# TEST-MODULE-V3.net
KiCad netlist of a schematic drawn in Altium Designer
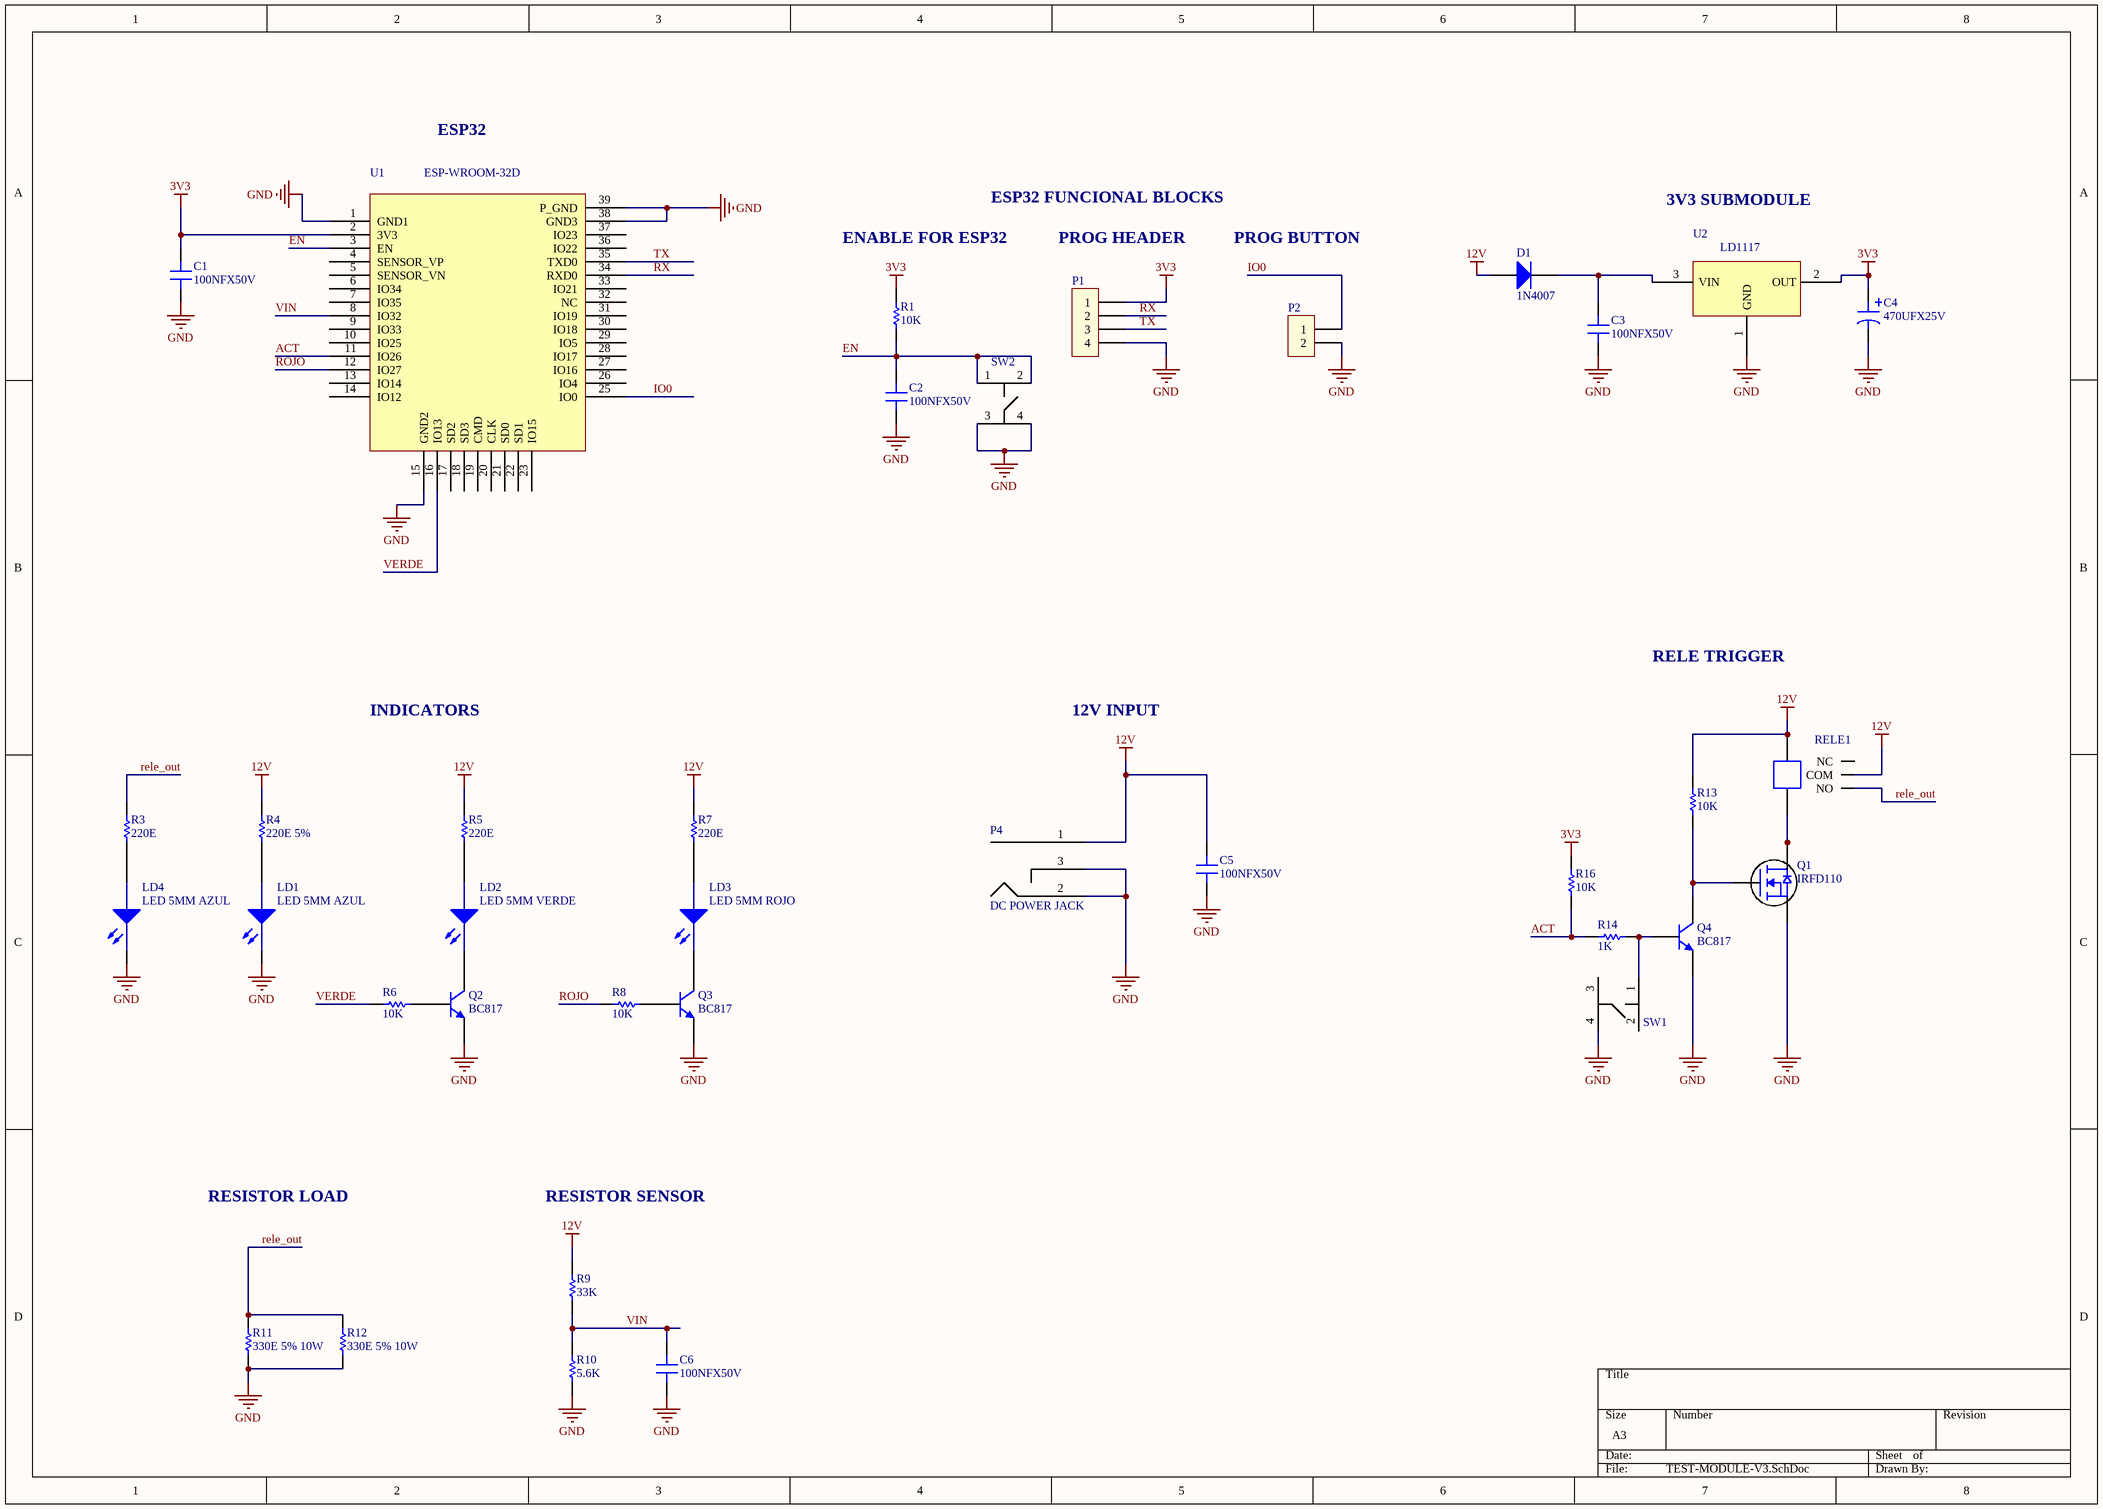
[diagram p0: TEST-MODULE-V3.SchDoc]

(export (version "E")
  (design (tool "Eeschema 10.0.6"))
  (components
    (comp (ref "C1")
      (value "100NFX50V")
      (footprint "CAP.SMD.0805")
      (description "100NFX50V X7R 10% CER.MULT. SMD 0805")
      (libsource (lib "Libreria-Capacitores") (part "Capacitor 100NFX50V X7R 10% CER.MULT. SMD 0805"))
    )
    (comp (ref "C2")
      (value "100NFX50V")
      (footprint "CAP.SMD.0805")
      (description "100NFX50V X7R 10% CER.MULT. SMD 0805")
      (libsource (lib "Libreria-Capacitores") (part "Capacitor 100NFX50V X7R 10% CER.MULT. SMD 0805"))
    )
    (comp (ref "C3")
      (value "100NFX50V")
      (footprint "CAP.SMD.0805")
      (description "100NFX50V X7R 10% CER.MULT. SMD 0805")
      (libsource (lib "Libreria-Capacitores") (part "Capacitor 100NFX50V X7R 10% CER.MULT. SMD 0805"))
    )
    (comp (ref "C4")
      (value "470UFX25V")
      (footprint "CAP-ELEC-10X13")
      (description "470UFX25V 85°C 10x13 ELE.RAD")
      (libsource (lib "Libreria-Capacitores") (part "Capacitor Electrolitico 470UFX25V 85°C 10x13 ELE.RAD"))
    )
    (comp (ref "C5")
      (value "100NFX50V")
      (footprint "CAP.SMD.0805")
      (description "100NFX50V X7R 10% CER.MULT. SMD 0805")
      (libsource (lib "Libreria-Capacitores") (part "Capacitor 100NFX50V X7R 10% CER.MULT. SMD 0805"))
    )
    (comp (ref "C6")
      (value "100NFX50V")
      (footprint "CAP.SMD.0805")
      (description "100NFX50V X7R 10% CER.MULT. SMD 0805")
      (libsource (lib "Libreria-Capacitores") (part "Capacitor 100NFX50V X7R 10% CER.MULT. SMD 0805"))
    )
    (comp (ref "D1")
      (value "1N4007")
      (footprint "Diode DO41")
      (description "Diodo 1N4007 DIODO 1A 1000V DO41")
      (libsource (lib "Libreria-Diodos") (part "Diodo 1N4007 DIODO 1A 1000V DO41"))
    )
    (comp (ref "LD1")
      (value "LED 5MM AZUL")
      (footprint "LED-5MM-ALTO-9-AZUL")
      (description "LED 5MM AZUL ALTO 9")
      (libsource (lib "Libreria-LEDs") (part "LED 5MM AZUL ALTO 9"))
    )
    (comp (ref "LD2")
      (value "LED 5MM VERDE")
      (footprint "LED-5MM-ALTO-9-VERDE")
      (description "LED 5MM VERDE ALTO 9")
      (libsource (lib "Libreria-LEDs") (part "LED 5MM VERDE ALTO 9"))
    )
    (comp (ref "LD3")
      (value "LED 5MM ROJO")
      (footprint "LED-5MM-ALTO-9-ROJO")
      (description "LED 5MM ROJO ALTO 9")
      (libsource (lib "Libreria-LEDs") (part "LED 5MM ROJO ALTO 9"))
    )
    (comp (ref "LD4")
      (value "LED 5MM AZUL")
      (footprint "LED-5MM-ALTO-9-AZUL")
      (description "LED 5MM AZUL ALTO 9")
      (libsource (lib "Libreria-LEDs") (part "LED 5MM AZUL ALTO 9"))
    )
    (comp (ref "P1")
      (value "IDC-HE-THT-1X4-P2.54MM")
      (footprint "IDC-HE-THT-1X4-P2.54MM")
      (libsource (lib "Libreria-Conectores") (part "IDC-HE-THT-1X4-P2.54MM"))
    )
    (comp (ref "P2")
      (value "IDC-MA-THT-1X2-P2.54MM-L11")
      (footprint "IDC-MA-THT-1X2-P2.54MM-L11")
      (libsource (lib "Libreria-Conectores") (part "IDC-MA-THT-1X2-P2.54MM-L11"))
    )
    (comp (ref "P4")
      (value "DC POWER JACK")
      (footprint "VAR-DC-JACK - VERT")
      (description "DC POWER JACK VERTICAL 2MM")
      (libsource (lib "Libreria-Varios") (part "DC POWER JACK VERTICAL 2MM"))
    )
    (comp (ref "Q1")
      (value "IRFD110")
      (footprint "TRA-IRFD110")
      (description "Transistor MOSFET N IRFD110")
      (libsource (lib "Libreria-Transistores") (part "Transistor MOSFET N IRFD110"))
    )
    (comp (ref "Q2")
      (value "BC817")
      (footprint "NPN.SMD.SOT23")
      (description "BC817-40 TRA.NPN 45V0.5A 0.25W SOT23")
      (libsource (lib "Libreria-Transistores") (part "Transistor BC817-40 TRA.NPN 45V0.5A 0.25W SOT23"))
    )
    (comp (ref "Q3")
      (value "BC817")
      (footprint "NPN.SMD.SOT23")
      (description "BC817-40 TRA.NPN 45V0.5A 0.25W SOT23")
      (libsource (lib "Libreria-Transistores") (part "Transistor BC817-40 TRA.NPN 45V0.5A 0.25W SOT23"))
    )
    (comp (ref "Q4")
      (value "BC817")
      (footprint "NPN.SMD.SOT23")
      (description "BC817-40 TRA.NPN 45V0.5A 0.25W SOT23")
      (libsource (lib "Libreria-Transistores") (part "Transistor BC817-40 TRA.NPN 45V0.5A 0.25W SOT23"))
    )
    (comp (ref "R1")
      (value "10K")
      (footprint "RES.SMD.103")
      (description "10K 5% 0805 1/8W RES.SMD")
      (libsource (lib "Libreria-Resistencias") (part "Resistencia 10K 5% 0805 1/8W"))
    )
    (comp (ref "R3")
      (value "220E")
      (footprint "RES.SMD.221")
      (description "220E 5% 0805 1/8W RES.SMD")
      (libsource (lib "Libreria-Resistencias") (part "Resistencia 220E 5% 0805 1/8W"))
    )
    (comp (ref "R4")
      (value "220E 5%")
      (footprint "RES.SMD.221")
      (description "220E 5% 0805 1/8W RES.SMD")
      (libsource (lib "Libreria-Resistencias") (part "Resistencia 220E 5% 0805 1/8W"))
    )
    (comp (ref "R5")
      (value "220E")
      (footprint "RES.SMD.221")
      (description "220E 5% 0805 1/8W RES.SMD")
      (libsource (lib "Libreria-Resistencias") (part "Resistencia 220E 5% 0805 1/8W"))
    )
    (comp (ref "R6")
      (value "10K")
      (footprint "RES.SMD.103")
      (description "10K 5% 0805 1/8W RES.SMD")
      (libsource (lib "Libreria-Resistencias") (part "Resistencia 10K 5% 0805 1/8W"))
    )
    (comp (ref "R7")
      (value "220E")
      (footprint "RES.SMD.221")
      (description "220E 5% 0805 1/8W RES.SMD")
      (libsource (lib "Libreria-Resistencias") (part "Resistencia 220E 5% 0805 1/8W"))
    )
    (comp (ref "R8")
      (value "10K")
      (footprint "RES.SMD.103")
      (description "10K 5% 0805 1/8W RES.SMD")
      (libsource (lib "Libreria-Resistencias") (part "Resistencia 10K 5% 0805 1/8W"))
    )
    (comp (ref "R9")
      (value "33K")
      (footprint "RES.SMD.333")
      (description "33K 5% 0805 1/8W RES.SMD")
      (libsource (lib "Libreria-Resistencias") (part "Resistencia 33K 5% 0805 1/8W"))
    )
    (comp (ref "R10")
      (value "5.6K")
      (footprint "RES.SMD.562")
      (description "5.6K 5% 0805 1/8W RES.SMD")
      (libsource (lib "Libreria-Resistencias") (part "Resistencia 5.6K 5% 0805 1/8W"))
    )
    (comp (ref "R11")
      (value "330E 5% 10W")
      (footprint "RES-CERAMICA-10W")
      (description "Resistencia Ceramica 330E 5% 10W SE15 RES.CEM")
      (libsource (lib "Libreria-Resistencias") (part "Resistencia Ceramica 330E 5% 10W SE15 RES.CEM"))
    )
    (comp (ref "R12")
      (value "330E 5% 10W")
      (footprint "RES-CERAMICA-10W")
      (description "Resistencia Ceramica 330E 5% 10W SE15 RES.CEM")
      (libsource (lib "Libreria-Resistencias") (part "Resistencia Ceramica 330E 5% 10W SE15 RES.CEM"))
    )
    (comp (ref "R13")
      (value "10K")
      (footprint "RES.SMD.103")
      (description "10K 5% 0805 1/8W RES.SMD")
      (libsource (lib "Libreria-Resistencias") (part "Resistencia 10K 5% 0805 1/8W"))
    )
    (comp (ref "R14")
      (value "1K")
      (footprint "RES.SMD.102")
      (description "1K 5% 0805 1/8W RES.SMD")
      (libsource (lib "Libreria-Resistencias") (part "Resistencia 1K 5% 0805 1/8W"))
    )
    (comp (ref "R16")
      (value "10K")
      (footprint "RES.SMD.103")
      (description "10K 5% 0805 1/8W RES.SMD")
      (libsource (lib "Libreria-Resistencias") (part "Resistencia 10K 5% 0805 1/8W"))
    )
    (comp (ref "RELE1")
      (value "Relay simple inversor 12V 12A")
      (footprint "RELAY 12V 12A CHICO")
      (libsource (lib "Libreria-Varios") (part "VAR-RELE-12V Relay simple inversor chico 12V 12A"))
    )
    (comp (ref "SW1")
      (value "TACT-SWITCH-THT-4C-06X06(13MM)-JIANFU")
      (footprint "TACT-SWITCH-THT-4C-06X06-13MM")
      (libsource (lib "Libreria-Switches") (part "TACT-SWITCH-THT-4C-06X06(13MM)-JIANFU"))
    )
    (comp (ref "SW2")
      (value "TACT-SWITCH-THT-4C-06X06(5MM)")
      (footprint "TACT-SWITCH-THT-4C-06X06-5MM")
      (libsource (lib "Libreria-Switches") (part "TACT-SWITCH-THT-4C-06X06(5MM)"))
    )
    (comp (ref "U1")
      (value "ESP32-WROOM-32D")
      (footprint "ESP32-WROOM-32D")
      (libsource (lib "Libreria-Semiconductores") (part "ESP32-WROOM-32D"))
    )
    (comp (ref "U2")
      (value "LD1117S33TR SMD DPAK 0.8A 3.3V LDO LINEAR REGULATOR")
      (footprint "DPAK")
      (libsource (lib "Libreria-Semiconductores") (part "LD1117S33TR SMD DPAK 0.8A 3.3V LDO LINEAR REGULATOR"))
    )
  )
  (nets
    (net (code "1") (name "/ACT") (class "Default")
      (node (ref "R14") (pin "1") (pinfunction "1_1") (pintype "passive"))
      (node (ref "R16") (pin "1") (pinfunction "1_1") (pintype "passive"))
      (node (ref "U1") (pin "11") (pinfunction "IO26_11") (pintype "passive"))
    )
    (net (code "2") (name "/EN") (class "Default")
      (node (ref "C2") (pin "2") (pinfunction "2_2") (pintype "passive"))
      (node (ref "R1") (pin "1") (pinfunction "1_1") (pintype "passive"))
      (node (ref "SW2") (pin "1") (pinfunction "1_1") (pintype "passive"))
      (node (ref "SW2") (pin "2") (pinfunction "2_2") (pintype "passive"))
      (node (ref "U1") (pin "3") (pinfunction "EN_3") (pintype "passive"))
    )
    (net (code "3") (name "/IO0") (class "Default")
      (node (ref "P2") (pin "1") (pinfunction "1_1") (pintype "passive"))
      (node (ref "U1") (pin "25") (pinfunction "IO0_25") (pintype "passive"))
    )
    (net (code "4") (name "/ROJO") (class "Default")
      (node (ref "R8") (pin "2") (pinfunction "2_2") (pintype "passive"))
      (node (ref "U1") (pin "12") (pinfunction "IO27_12") (pintype "passive"))
    )
    (net (code "5") (name "/RX") (class "Default")
      (node (ref "P1") (pin "2") (pinfunction "2_2") (pintype "passive"))
      (node (ref "U1") (pin "34") (pinfunction "RXD0_34") (pintype "passive"))
    )
    (net (code "6") (name "/TX") (class "Default")
      (node (ref "P1") (pin "3") (pinfunction "3_3") (pintype "passive"))
      (node (ref "U1") (pin "35") (pinfunction "TXD0_35") (pintype "passive"))
    )
    (net (code "7") (name "/VERDE") (class "Default")
      (node (ref "R6") (pin "1") (pinfunction "1_1") (pintype "passive"))
      (node (ref "U1") (pin "16") (pinfunction "IO13_16") (pintype "passive"))
    )
    (net (code "8") (name "/VIN") (class "Default")
      (node (ref "C6") (pin "2") (pinfunction "2_2") (pintype "passive"))
      (node (ref "R10") (pin "2") (pinfunction "2_2") (pintype "passive"))
      (node (ref "R9") (pin "1") (pinfunction "1_1") (pintype "passive"))
      (node (ref "U1") (pin "8") (pinfunction "IO32_8") (pintype "passive"))
    )
    (net (code "9") (name "/rele_out") (class "Default")
      (node (ref "R11") (pin "2") (pinfunction "2_2") (pintype "passive"))
      (node (ref "R12") (pin "2") (pinfunction "2_2") (pintype "passive"))
      (node (ref "R3") (pin "2") (pinfunction "2_2") (pintype "passive"))
      (node (ref "RELE1") (pin "4") (pinfunction "NO_4") (pintype "passive"))
    )
    (net (code "10") (name "3V3") (class "Default")
      (node (ref "C1") (pin "2") (pinfunction "2_2") (pintype "passive"))
      (node (ref "C4") (pin "1") (pinfunction "1_1") (pintype "passive"))
      (node (ref "P1") (pin "1") (pinfunction "1_1") (pintype "passive"))
      (node (ref "R1") (pin "2") (pinfunction "2_2") (pintype "passive"))
      (node (ref "R16") (pin "2") (pinfunction "2_2") (pintype "passive"))
      (node (ref "U1") (pin "2") (pinfunction "3V3_2") (pintype "passive"))
      (node (ref "U2") (pin "2") (pinfunction "OUT_2") (pintype "passive"))
    )
    (net (code "11") (name "12V") (class "Default")
      (node (ref "C5") (pin "2") (pinfunction "2_2") (pintype "passive"))
      (node (ref "D1") (pin "A") (pinfunction "A_A") (pintype "passive"))
      (node (ref "P4") (pin "1") (pinfunction "1_1") (pintype "passive"))
      (node (ref "R13") (pin "2") (pinfunction "2_2") (pintype "passive"))
      (node (ref "R4") (pin "2") (pinfunction "2_2") (pintype "passive"))
      (node (ref "R5") (pin "2") (pinfunction "2_2") (pintype "passive"))
      (node (ref "R7") (pin "2") (pinfunction "2_2") (pintype "passive"))
      (node (ref "R9") (pin "2") (pinfunction "2_2") (pintype "passive"))
      (node (ref "RELE1") (pin "1") (pinfunction "1_1") (pintype "passive"))
      (node (ref "RELE1") (pin "3") (pinfunction "COM_3") (pintype "passive"))
    )
    (net (code "12") (name "GND") (class "Default")
      (node (ref "C1") (pin "1") (pinfunction "1_1") (pintype "passive"))
      (node (ref "C2") (pin "1") (pinfunction "1_1") (pintype "passive"))
      (node (ref "C3") (pin "1") (pinfunction "1_1") (pintype "passive"))
      (node (ref "C4") (pin "2") (pinfunction "2_2") (pintype "passive"))
      (node (ref "C5") (pin "1") (pinfunction "1_1") (pintype "passive"))
      (node (ref "C6") (pin "1") (pinfunction "1_1") (pintype "passive"))
      (node (ref "LD1") (pin "K") (pinfunction "KB_K") (pintype "passive"))
      (node (ref "LD4") (pin "K") (pinfunction "KB_K") (pintype "passive"))
      (node (ref "P1") (pin "4") (pinfunction "4_4") (pintype "passive"))
      (node (ref "P2") (pin "2") (pinfunction "2_2") (pintype "passive"))
      (node (ref "P4") (pin "2") (pinfunction "2_2") (pintype "passive"))
      (node (ref "P4") (pin "3") (pinfunction "3_3") (pintype "passive"))
      (node (ref "Q1") (pin "4") (pinfunction "4_4") (pintype "passive"))
      (node (ref "Q2") (pin "2") (pinfunction "E_2") (pintype "passive"))
      (node (ref "Q3") (pin "2") (pinfunction "E_2") (pintype "passive"))
      (node (ref "Q4") (pin "2") (pinfunction "E_2") (pintype "passive"))
      (node (ref "R10") (pin "1") (pinfunction "1_1") (pintype "passive"))
      (node (ref "R11") (pin "1") (pinfunction "1_1") (pintype "passive"))
      (node (ref "R12") (pin "1") (pinfunction "1_1") (pintype "passive"))
      (node (ref "SW1") (pin "4") (pinfunction "4_4") (pintype "passive"))
      (node (ref "SW2") (pin "3") (pinfunction "3_3") (pintype "passive"))
      (node (ref "SW2") (pin "4") (pinfunction "4_4") (pintype "passive"))
      (node (ref "U1") (pin "1") (pinfunction "GND1_1") (pintype "passive"))
      (node (ref "U1") (pin "15") (pinfunction "GND2_15") (pintype "passive"))
      (node (ref "U1") (pin "38") (pinfunction "GND3_38") (pintype "passive"))
      (node (ref "U1") (pin "39") (pinfunction "P_GND_39") (pintype "passive"))
      (node (ref "U2") (pin "1") (pinfunction "GND_1") (pintype "passive"))
    )
    (net (code "13") (name "Net-(LD1-AB)") (class "Default")
      (node (ref "LD1") (pin "A") (pinfunction "AB_A") (pintype "passive"))
      (node (ref "R4") (pin "1") (pinfunction "1_1") (pintype "passive"))
    )
    (net (code "14") (name "Net-(LD2-AB)") (class "Default")
      (node (ref "LD2") (pin "A") (pinfunction "AB_A") (pintype "passive"))
      (node (ref "R5") (pin "1") (pinfunction "1_1") (pintype "passive"))
    )
    (net (code "15") (name "Net-(LD2-KB)") (class "Default")
      (node (ref "LD2") (pin "K") (pinfunction "KB_K") (pintype "passive"))
      (node (ref "Q2") (pin "3") (pinfunction "C_3") (pintype "passive"))
    )
    (net (code "16") (name "Net-(LD3-AB)") (class "Default")
      (node (ref "LD3") (pin "A") (pinfunction "AB_A") (pintype "passive"))
      (node (ref "R7") (pin "1") (pinfunction "1_1") (pintype "passive"))
    )
    (net (code "17") (name "Net-(LD3-KB)") (class "Default")
      (node (ref "LD3") (pin "K") (pinfunction "KB_K") (pintype "passive"))
      (node (ref "Q3") (pin "3") (pinfunction "C_3") (pintype "passive"))
    )
    (net (code "18") (name "Net-(LD4-AB)") (class "Default")
      (node (ref "LD4") (pin "A") (pinfunction "AB_A") (pintype "passive"))
      (node (ref "R3") (pin "1") (pinfunction "1_1") (pintype "passive"))
    )
    (net (code "19") (name "Net-(Q1-Pad1)") (class "Default")
      (node (ref "Q1") (pin "1") (pinfunction "1_1") (pintype "passive"))
      (node (ref "Q1") (pin "2") (pinfunction "2_2") (pintype "passive"))
      (node (ref "RELE1") (pin "2") (pinfunction "2_2") (pintype "passive"))
    )
    (net (code "20") (name "Net-(Q2-B)") (class "Default")
      (node (ref "Q2") (pin "1") (pinfunction "B_1") (pintype "passive"))
      (node (ref "R6") (pin "2") (pinfunction "2_2") (pintype "passive"))
    )
    (net (code "21") (name "Net-(Q3-B)") (class "Default")
      (node (ref "Q3") (pin "1") (pinfunction "B_1") (pintype "passive"))
      (node (ref "R8") (pin "1") (pinfunction "1_1") (pintype "passive"))
    )
    (net (code "22") (name "Net-(Q4-B)") (class "Default")
      (node (ref "Q4") (pin "1") (pinfunction "B_1") (pintype "passive"))
      (node (ref "R14") (pin "2") (pinfunction "2_2") (pintype "passive"))
      (node (ref "SW1") (pin "1") (pinfunction "1_1") (pintype "passive"))
    )
    (net (code "23") (name "Net-(Q4-C)") (class "Default")
      (node (ref "Q1") (pin "3") (pinfunction "3_3") (pintype "passive"))
      (node (ref "Q4") (pin "3") (pinfunction "C_3") (pintype "passive"))
      (node (ref "R13") (pin "1") (pinfunction "1_1") (pintype "passive"))
    )
    (net (code "24") (name "Net-(U2-VIN)") (class "Default")
      (node (ref "C3") (pin "2") (pinfunction "2_2") (pintype "passive"))
      (node (ref "D1") (pin "K") (pinfunction "K_K") (pintype "passive"))
      (node (ref "U2") (pin "3") (pinfunction "VIN_3") (pintype "passive"))
    )
    (net (code "25") (name "unconnected-(RELE1-NC-Pad5)") (class "Default")
      (node (ref "RELE1") (pin "5") (pinfunction "NC_5") (pintype "passive"))
    )
    (net (code "26") (name "unconnected-(SW1-Pad2)") (class "Default")
      (node (ref "SW1") (pin "2") (pinfunction "2_2") (pintype "passive"))
    )
    (net (code "27") (name "unconnected-(SW1-Pad3)") (class "Default")
      (node (ref "SW1") (pin "3") (pinfunction "3_3") (pintype "passive"))
    )
    (net (code "28") (name "unconnected-(U1-CLK-Pad20)") (class "Default")
      (node (ref "U1") (pin "20") (pinfunction "CLK_20") (pintype "passive"))
    )
    (net (code "29") (name "unconnected-(U1-CMD-Pad19)") (class "Default")
      (node (ref "U1") (pin "19") (pinfunction "CMD_19") (pintype "passive"))
    )
    (net (code "30") (name "unconnected-(U1-IO4-Pad26)") (class "Default")
      (node (ref "U1") (pin "26") (pinfunction "IO4_26") (pintype "passive"))
    )
    (net (code "31") (name "unconnected-(U1-IO5-Pad29)") (class "Default")
      (node (ref "U1") (pin "29") (pinfunction "IO5_29") (pintype "passive"))
    )
    (net (code "32") (name "unconnected-(U1-IO12-Pad14)") (class "Default")
      (node (ref "U1") (pin "14") (pinfunction "IO12_14") (pintype "passive"))
    )
    (net (code "33") (name "unconnected-(U1-IO14-Pad13)") (class "Default")
      (node (ref "U1") (pin "13") (pinfunction "IO14_13") (pintype "passive"))
    )
    (net (code "34") (name "unconnected-(U1-IO15-Pad23)") (class "Default")
      (node (ref "U1") (pin "23") (pinfunction "IO15_23") (pintype "passive"))
    )
    (net (code "35") (name "unconnected-(U1-IO16-Pad27)") (class "Default")
      (node (ref "U1") (pin "27") (pinfunction "IO16_27") (pintype "passive"))
    )
    (net (code "36") (name "unconnected-(U1-IO17-Pad28)") (class "Default")
      (node (ref "U1") (pin "28") (pinfunction "IO17_28") (pintype "passive"))
    )
    (net (code "37") (name "unconnected-(U1-IO18-Pad30)") (class "Default")
      (node (ref "U1") (pin "30") (pinfunction "IO18_30") (pintype "passive"))
    )
    (net (code "38") (name "unconnected-(U1-IO19-Pad31)") (class "Default")
      (node (ref "U1") (pin "31") (pinfunction "IO19_31") (pintype "passive"))
    )
    (net (code "39") (name "unconnected-(U1-IO21-Pad33)") (class "Default")
      (node (ref "U1") (pin "33") (pinfunction "IO21_33") (pintype "passive"))
    )
    (net (code "40") (name "unconnected-(U1-IO22-Pad36)") (class "Default")
      (node (ref "U1") (pin "36") (pinfunction "IO22_36") (pintype "passive"))
    )
    (net (code "41") (name "unconnected-(U1-IO23-Pad37)") (class "Default")
      (node (ref "U1") (pin "37") (pinfunction "IO23_37") (pintype "passive"))
    )
    (net (code "42") (name "unconnected-(U1-IO25-Pad10)") (class "Default")
      (node (ref "U1") (pin "10") (pinfunction "IO25_10") (pintype "passive"))
    )
    (net (code "43") (name "unconnected-(U1-IO33-Pad9)") (class "Default")
      (node (ref "U1") (pin "9") (pinfunction "IO33_9") (pintype "passive"))
    )
    (net (code "44") (name "unconnected-(U1-IO34-Pad6)") (class "Default")
      (node (ref "U1") (pin "6") (pinfunction "IO34_6") (pintype "passive"))
    )
    (net (code "45") (name "unconnected-(U1-IO35-Pad7)") (class "Default")
      (node (ref "U1") (pin "7") (pinfunction "IO35_7") (pintype "passive"))
    )
    (net (code "46") (name "unconnected-(U1-NC-Pad32)") (class "Default")
      (node (ref "U1") (pin "32") (pinfunction "NC_32") (pintype "passive"))
    )
    (net (code "47") (name "unconnected-(U1-SD0-Pad21)") (class "Default")
      (node (ref "U1") (pin "21") (pinfunction "SD0_21") (pintype "passive"))
    )
    (net (code "48") (name "unconnected-(U1-SD1-Pad22)") (class "Default")
      (node (ref "U1") (pin "22") (pinfunction "SD1_22") (pintype "passive"))
    )
    (net (code "49") (name "unconnected-(U1-SD2-Pad17)") (class "Default")
      (node (ref "U1") (pin "17") (pinfunction "SD2_17") (pintype "passive"))
    )
    (net (code "50") (name "unconnected-(U1-SD3-Pad18)") (class "Default")
      (node (ref "U1") (pin "18") (pinfunction "SD3_18") (pintype "passive"))
    )
    (net (code "51") (name "unconnected-(U1-SENSOR_VN-Pad5)") (class "Default")
      (node (ref "U1") (pin "5") (pinfunction "SENSOR_VN_5") (pintype "passive"))
    )
    (net (code "52") (name "unconnected-(U1-SENSOR_VP-Pad4)") (class "Default")
      (node (ref "U1") (pin "4") (pinfunction "SENSOR_VP_4") (pintype "passive"))
    )
  )
)
